# updi_serial.net
KiCad netlist of a schematic drawn in EAGLE
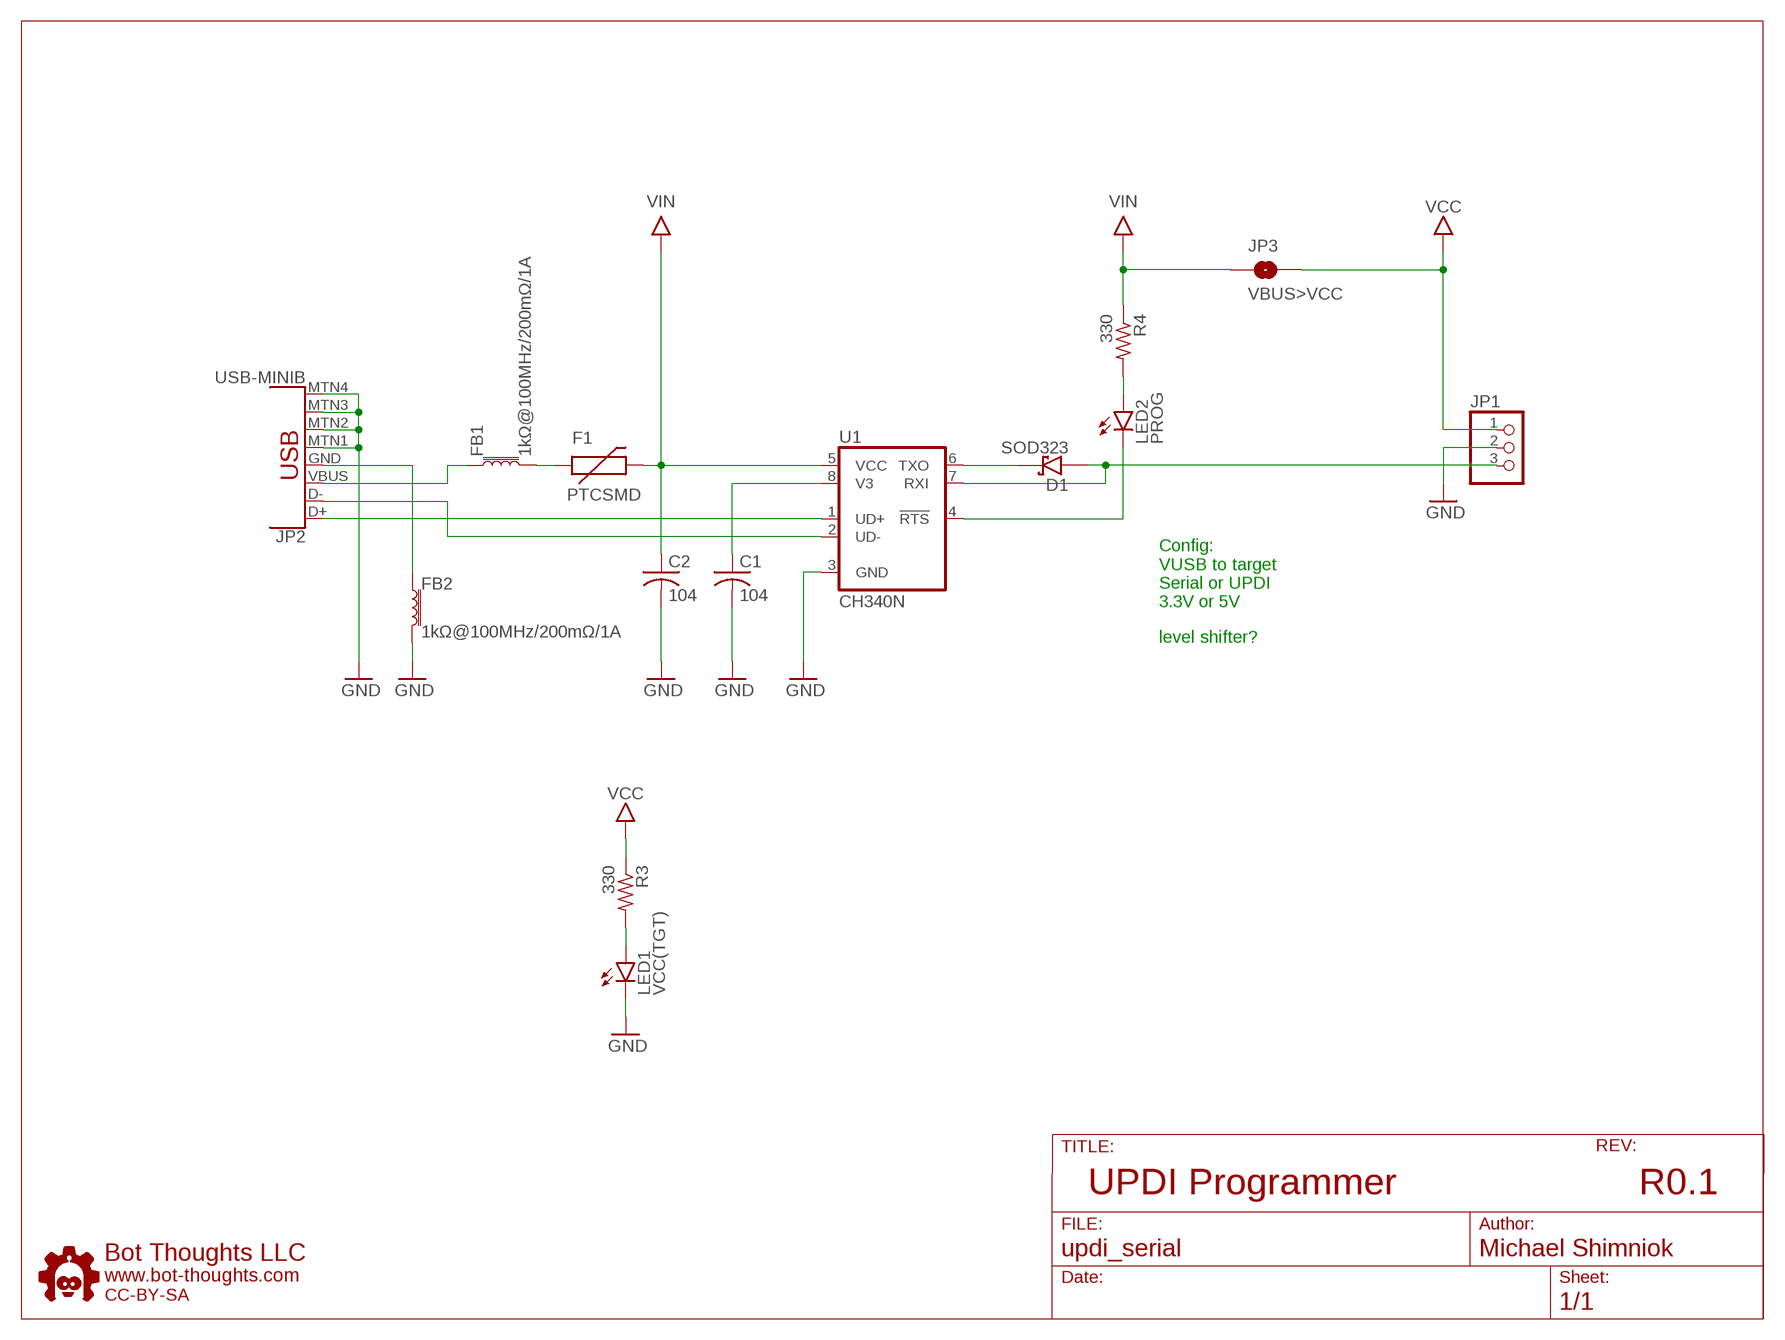
[diagram p0: schematic, sheet 1]

(export (version "E")
  (design (tool "Eeschema 10.0.6"))
  (components
    (comp (ref "C1")
      (value "104")
      (footprint "eagle-import:0603")
      (libsource (lib "eagle-import") (part "C-0603"))
    )
    (comp (ref "C2")
      (value "104")
      (footprint "eagle-import:0603")
      (libsource (lib "eagle-import") (part "C-0603"))
    )
    (comp (ref "D1")
      (value "SOD323")
      (footprint "eagle-import:SOD123FL")
      (libsource (lib "eagle-import") (part "SCHOTTKY-DIODE-MBR130LSFT1"))
    )
    (comp (ref "F1")
      (value "PTCSMD")
      (footprint "eagle-import:PTC-1206")
      (libsource (lib "eagle-import") (part "PTCSMD"))
    )
    (comp (ref "FB1")
      (value "1kΩ@100MHz/200mΩ/1A")
      (footprint "eagle-import:0603")
      (libsource (lib "eagle-import") (part "FERRITE_BEAD-0603"))
    )
    (comp (ref "FB2")
      (value "1kΩ@100MHz/200mΩ/1A")
      (footprint "eagle-import:0603")
      (libsource (lib "eagle-import") (part "FERRITE_BEAD-0603"))
    )
    (comp (ref "JP1")
      (value "PINHD-1X03_2.54-S")
      (footprint "eagle-import:1X03-S")
      (libsource (lib "eagle-import") (part "PINHD-1X03_2.54-S"))
    )
    (comp (ref "JP2")
      (value "USB-MINIB")
      (footprint "eagle-import:USB-MINIB")
      (libsource (lib "eagle-import") (part "USB-MINIB"))
    )
    (comp (ref "JP3")
      (value "VBUS>VCC")
      (footprint "eagle-import:JUMPER-PIN-0.1IN")
      (libsource (lib "eagle-import") (part "JUMPER-PTH-0.1IN"))
    )
    (comp (ref "LED1")
      (value "VCC(TGT)")
      (footprint "eagle-import:CHIPLED_1206")
      (libsource (lib "eagle-import") (part "LEDCHIPLED_1206"))
    )
    (comp (ref "LED2")
      (value "PROG")
      (footprint "eagle-import:CHIPLED_1206")
      (libsource (lib "eagle-import") (part "LEDCHIPLED_1206"))
    )
    (comp (ref "R3")
      (value "330")
      (footprint "eagle-import:0603")
      (libsource (lib "eagle-import") (part "R0603"))
    )
    (comp (ref "R4")
      (value "330")
      (footprint "eagle-import:0603")
      (libsource (lib "eagle-import") (part "R0603"))
    )
    (comp (ref "U$5")
      (value "BTLOGO-LOGO-SM")
      (footprint "eagle-import:BTLOGOS")
      (libsource (lib "eagle-import") (part "BTLOGO-LOGO-SM"))
    )
    (comp (ref "U1")
      (value "CH340N")
      (footprint "eagle-import:SOIC8N")
      (libsource (lib "eagle-import") (part "CH340N"))
    )
  )
  (nets
    (net (code "1") (name "GND") (class "Default")
      (node (ref "C1") (pin "2") (pinfunction "-_2") (pintype "passive"))
      (node (ref "C2") (pin "2") (pinfunction "-_2") (pintype "passive"))
      (node (ref "FB2") (pin "2") (pinfunction "2_2") (pintype "passive"))
      (node (ref "JP1") (pin "2") (pinfunction "2_2") (pintype "passive"))
      (node (ref "JP2") (pin "MTN1") (pinfunction "SHIELD1_MTN1") (pintype "bidirectional"))
      (node (ref "JP2") (pin "MTN2") (pinfunction "SHIELD2_MTN2") (pintype "bidirectional"))
      (node (ref "JP2") (pin "MTN3") (pinfunction "SHIELD3_MTN3") (pintype "bidirectional"))
      (node (ref "JP2") (pin "MTN4") (pinfunction "SHIELD4_MTN4") (pintype "bidirectional"))
      (node (ref "LED1") (pin "C") (pinfunction "C_C") (pintype "passive"))
      (node (ref "U1") (pin "3") (pinfunction "GND_3") (pintype "bidirectional"))
    )
    (net (code "2") (name "Net-(C1-+)") (class "Default")
      (node (ref "C1") (pin "1") (pinfunction "+_1") (pintype "passive"))
      (node (ref "U1") (pin "8") (pinfunction "V3_8") (pintype "bidirectional"))
    )
    (net (code "3") (name "Net-(F1-Pad1)") (class "Default")
      (node (ref "F1") (pin "1") (pinfunction "1_1") (pintype "bidirectional"))
      (node (ref "FB1") (pin "2") (pinfunction "2_2") (pintype "passive"))
    )
    (net (code "4") (name "Net-(FB1-Pad1)") (class "Default")
      (node (ref "FB1") (pin "1") (pinfunction "1_1") (pintype "passive"))
      (node (ref "JP2") (pin "VBUS") (pinfunction "VBUS_VBUS") (pintype "bidirectional"))
    )
    (net (code "5") (name "Net-(FB2-Pad1)") (class "Default")
      (node (ref "FB2") (pin "1") (pinfunction "1_1") (pintype "passive"))
      (node (ref "JP2") (pin "GND") (pinfunction "GND_GND") (pintype "bidirectional"))
    )
    (net (code "6") (name "Net-(LED1-PadA)") (class "Default")
      (node (ref "LED1") (pin "A") (pinfunction "A_A") (pintype "passive"))
      (node (ref "R3") (pin "2") (pinfunction "2_2") (pintype "passive"))
    )
    (net (code "7") (name "Net-(LED2-PadA)") (class "Default")
      (node (ref "LED2") (pin "A") (pinfunction "A_A") (pintype "passive"))
      (node (ref "R4") (pin "2") (pinfunction "2_2") (pintype "passive"))
    )
    (net (code "8") (name "Net-(U1-RXI)") (class "Default")
      (node (ref "D1") (pin "A") (pinfunction "A_A") (pintype "passive"))
      (node (ref "JP1") (pin "3") (pinfunction "3_3") (pintype "passive"))
      (node (ref "U1") (pin "7") (pinfunction "RXI_7") (pintype "bidirectional"))
    )
    (net (code "9") (name "Net-(U1-TXO)") (class "Default")
      (node (ref "D1") (pin "C") (pinfunction "C_C") (pintype "passive"))
      (node (ref "U1") (pin "6") (pinfunction "TXO_6") (pintype "bidirectional"))
    )
    (net (code "10") (name "Net-(U1-UD+)") (class "Default")
      (node (ref "JP2") (pin "D+") (pinfunction "D+_D+") (pintype "bidirectional"))
      (node (ref "U1") (pin "1") (pinfunction "UD+_1") (pintype "bidirectional"))
    )
    (net (code "11") (name "Net-(U1-UD-)") (class "Default")
      (node (ref "JP2") (pin "D-") (pinfunction "D-_D-") (pintype "bidirectional"))
      (node (ref "U1") (pin "2") (pinfunction "UD-_2") (pintype "bidirectional"))
    )
    (net (code "12") (name "Net-(U1-~{RTS})") (class "Default")
      (node (ref "LED2") (pin "C") (pinfunction "C_C") (pintype "passive"))
      (node (ref "U1") (pin "4") (pinfunction "~{RTS}_4") (pintype "bidirectional"))
    )
    (net (code "13") (name "VCC") (class "Default")
      (node (ref "JP1") (pin "1") (pinfunction "1_1") (pintype "passive"))
      (node (ref "JP3") (pin "2") (pinfunction "2_2") (pintype "passive"))
      (node (ref "R3") (pin "1") (pinfunction "1_1") (pintype "passive"))
    )
    (net (code "14") (name "VIN") (class "Default")
      (node (ref "C2") (pin "1") (pinfunction "+_1") (pintype "passive"))
      (node (ref "F1") (pin "2") (pinfunction "2_2") (pintype "bidirectional"))
      (node (ref "JP3") (pin "1") (pinfunction "1_1") (pintype "passive"))
      (node (ref "R4") (pin "1") (pinfunction "1_1") (pintype "passive"))
      (node (ref "U1") (pin "5") (pinfunction "VCC_5") (pintype "bidirectional"))
    )
  )
)
